# 06-1G_Phy0.net
KiCad netlist of a schematic drawn in Altium Designer
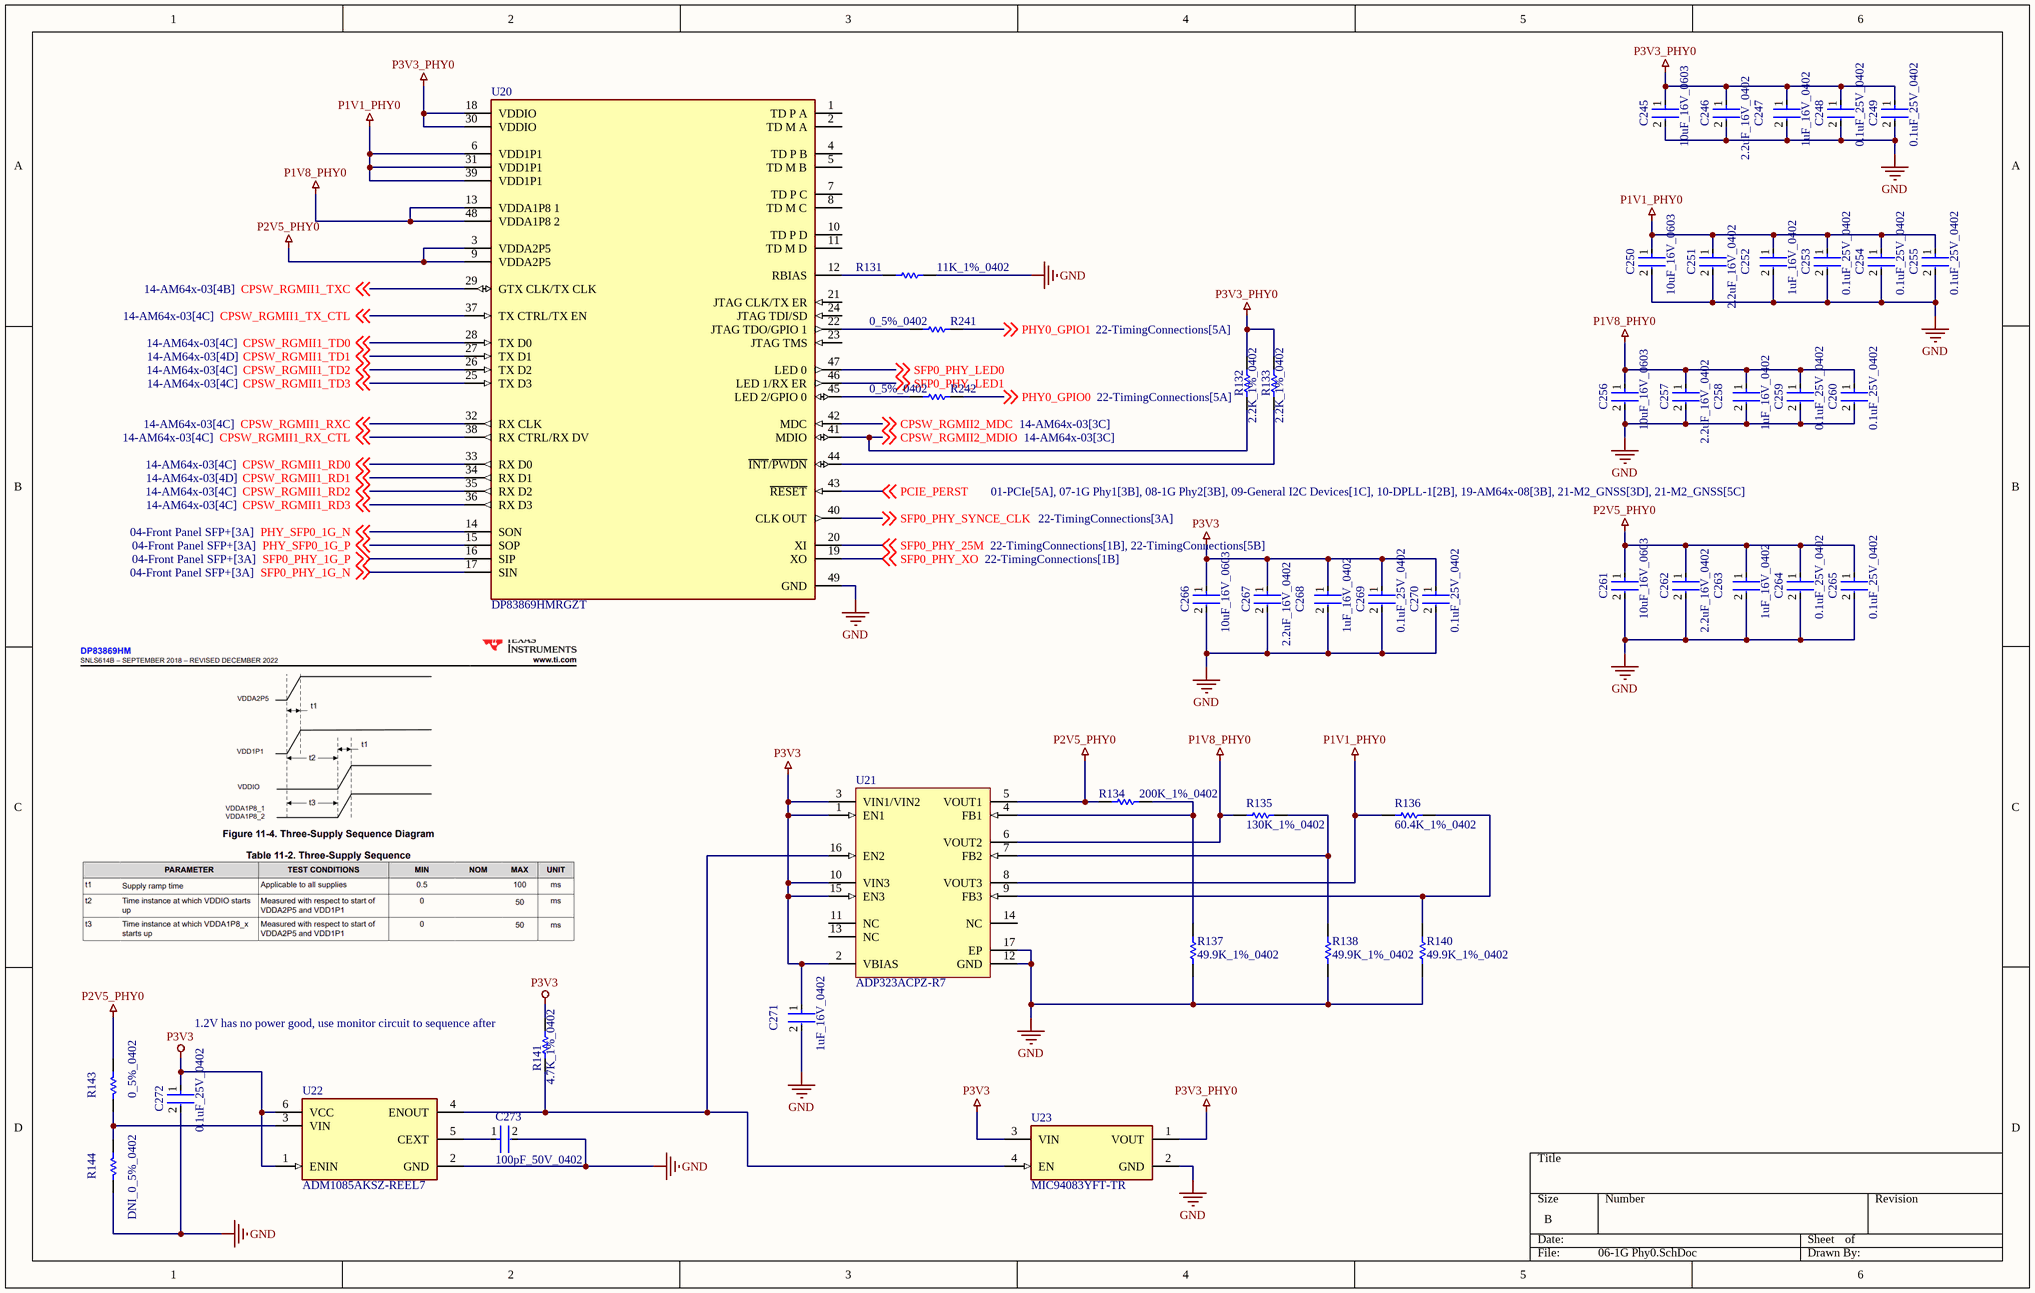
[diagram p0: 06-1G Phy0.SchDoc]

(export (version "E")
  (design (tool "Eeschema 10.0.6"))
  (components
    (comp (ref "C245")
      (value "10uF_16V_0603")
      (footprint "FP-0603-L_1_6_0_2-W_0_8_0-MFG")
      (description "Multilayer Ceramic Capacitor 10uF 16V X5R 20% SMD 0603 T/R")
      (fields (field (name "TOLERANCE") "20%"))
      (libsource (lib "Altium Content Vault") (part "b4654b650e69147ec39a6b967a45e02"))
    )
    (comp (ref "C246")
      (value "2.2uF_16V_0402")
      (footprint "FP-C1005-050-0_05-IPC_A")
      (description "Multilayer Ceramic Capacitors 2.2μF ±10% 16V X5R SMD 0402")
      (fields (field (name "TOLERANCE") "10%"))
      (libsource (lib "Altium Content Vault") (part "b4654b650e69147ec39a6b967a45e02"))
    )
    (comp (ref "C247")
      (value "1uF_16V_0402")
      (footprint "FP-0402-L_1_0_0_05-W_0_5-IPC_A")
      (description "None")
      (fields (field (name "TOLERANCE") "10%"))
      (libsource (lib "Altium Content Vault") (part "b4654b650e69147ec39a6b967a45e02"))
    )
    (comp (ref "C248")
      (value "0.1uF_25V_0402")
      (footprint "FP-0402-L_1_0_1-W_0_5_0_1-IPC_C")
      (description "General Purpose Ceramic Capacitor, 0402, 100nF, 10%, X7R, 15%, 25V")
      (fields (field (name "VOLTAGE") "25V") (field (name "TOLERANCE") "10%"))
      (libsource (lib "Altium Content Vault") (part "b4654b650e69147ec39a6b967a45e02"))
    )
    (comp (ref "C249")
      (value "0.1uF_25V_0402")
      (footprint "FP-0402-L_1_0_1-W_0_5_0_1-IPC_C")
      (description "General Purpose Ceramic Capacitor, 0402, 100nF, 10%, X7R, 15%, 25V")
      (fields (field (name "VOLTAGE") "25V") (field (name "TOLERANCE") "10%"))
      (libsource (lib "Altium Content Vault") (part "b4654b650e69147ec39a6b967a45e02"))
    )
    (comp (ref "C250")
      (value "10uF_16V_0603")
      (footprint "FP-0603-L_1_6_0_2-W_0_8_0-MFG")
      (description "Multilayer Ceramic Capacitor 10uF 16V X5R 20% SMD 0603 T/R")
      (fields (field (name "TOLERANCE") "20%"))
      (libsource (lib "Altium Content Vault") (part "b4654b650e69147ec39a6b967a45e02"))
    )
    (comp (ref "C251")
      (value "2.2uF_16V_0402")
      (footprint "FP-C1005-050-0_05-IPC_A")
      (description "Multilayer Ceramic Capacitors 2.2μF ±10% 16V X5R SMD 0402")
      (fields (field (name "TOLERANCE") "10%"))
      (libsource (lib "Altium Content Vault") (part "b4654b650e69147ec39a6b967a45e02"))
    )
    (comp (ref "C252")
      (value "1uF_16V_0402")
      (footprint "FP-0402-L_1_0_0_05-W_0_5-IPC_A")
      (description "None")
      (fields (field (name "TOLERANCE") "10%"))
      (libsource (lib "Altium Content Vault") (part "b4654b650e69147ec39a6b967a45e02"))
    )
    (comp (ref "C253")
      (value "0.1uF_25V_0402")
      (footprint "FP-0402-L_1_0_1-W_0_5_0_1-IPC_C")
      (description "General Purpose Ceramic Capacitor, 0402, 100nF, 10%, X7R, 15%, 25V")
      (fields (field (name "VOLTAGE") "25V") (field (name "TOLERANCE") "10%"))
      (libsource (lib "Altium Content Vault") (part "b4654b650e69147ec39a6b967a45e02"))
    )
    (comp (ref "C254")
      (value "0.1uF_25V_0402")
      (footprint "FP-0402-L_1_0_1-W_0_5_0_1-IPC_C")
      (description "General Purpose Ceramic Capacitor, 0402, 100nF, 10%, X7R, 15%, 25V")
      (fields (field (name "VOLTAGE") "25V") (field (name "TOLERANCE") "10%"))
      (libsource (lib "Altium Content Vault") (part "b4654b650e69147ec39a6b967a45e02"))
    )
    (comp (ref "C255")
      (value "0.1uF_25V_0402")
      (footprint "FP-0402-L_1_0_1-W_0_5_0_1-IPC_C")
      (description "General Purpose Ceramic Capacitor, 0402, 100nF, 10%, X7R, 15%, 25V")
      (fields (field (name "VOLTAGE") "25V") (field (name "TOLERANCE") "10%"))
      (libsource (lib "Altium Content Vault") (part "b4654b650e69147ec39a6b967a45e02"))
    )
    (comp (ref "C256")
      (value "10uF_16V_0603")
      (footprint "FP-0603-L_1_6_0_2-W_0_8_0-MFG")
      (description "Multilayer Ceramic Capacitor 10uF 16V X5R 20% SMD 0603 T/R")
      (fields (field (name "TOLERANCE") "20%"))
      (libsource (lib "Altium Content Vault") (part "b4654b650e69147ec39a6b967a45e02"))
    )
    (comp (ref "C257")
      (value "2.2uF_16V_0402")
      (footprint "FP-C1005-050-0_05-IPC_A")
      (description "Multilayer Ceramic Capacitors 2.2μF ±10% 16V X5R SMD 0402")
      (fields (field (name "TOLERANCE") "10%"))
      (libsource (lib "Altium Content Vault") (part "b4654b650e69147ec39a6b967a45e02"))
    )
    (comp (ref "C258")
      (value "1uF_16V_0402")
      (footprint "FP-0402-L_1_0_0_05-W_0_5-IPC_A")
      (description "None")
      (fields (field (name "TOLERANCE") "10%"))
      (libsource (lib "Altium Content Vault") (part "b4654b650e69147ec39a6b967a45e02"))
    )
    (comp (ref "C259")
      (value "0.1uF_25V_0402")
      (footprint "FP-0402-L_1_0_1-W_0_5_0_1-IPC_C")
      (description "General Purpose Ceramic Capacitor, 0402, 100nF, 10%, X7R, 15%, 25V")
      (fields (field (name "VOLTAGE") "25V") (field (name "TOLERANCE") "10%"))
      (libsource (lib "Altium Content Vault") (part "b4654b650e69147ec39a6b967a45e02"))
    )
    (comp (ref "C260")
      (value "0.1uF_25V_0402")
      (footprint "FP-0402-L_1_0_1-W_0_5_0_1-IPC_C")
      (description "General Purpose Ceramic Capacitor, 0402, 100nF, 10%, X7R, 15%, 25V")
      (fields (field (name "VOLTAGE") "25V") (field (name "TOLERANCE") "10%"))
      (libsource (lib "Altium Content Vault") (part "b4654b650e69147ec39a6b967a45e02"))
    )
    (comp (ref "C261")
      (value "10uF_16V_0603")
      (footprint "FP-0603-L_1_6_0_2-W_0_8_0-MFG")
      (description "Multilayer Ceramic Capacitor 10uF 16V X5R 20% SMD 0603 T/R")
      (fields (field (name "TOLERANCE") "20%"))
      (libsource (lib "Altium Content Vault") (part "b4654b650e69147ec39a6b967a45e02"))
    )
    (comp (ref "C262")
      (value "2.2uF_16V_0402")
      (footprint "FP-C1005-050-0_05-IPC_A")
      (description "Multilayer Ceramic Capacitors 2.2μF ±10% 16V X5R SMD 0402")
      (fields (field (name "TOLERANCE") "10%"))
      (libsource (lib "Altium Content Vault") (part "b4654b650e69147ec39a6b967a45e02"))
    )
    (comp (ref "C263")
      (value "1uF_16V_0402")
      (footprint "FP-0402-L_1_0_0_05-W_0_5-IPC_A")
      (description "None")
      (fields (field (name "TOLERANCE") "10%"))
      (libsource (lib "Altium Content Vault") (part "b4654b650e69147ec39a6b967a45e02"))
    )
    (comp (ref "C264")
      (value "0.1uF_25V_0402")
      (footprint "FP-0402-L_1_0_1-W_0_5_0_1-IPC_C")
      (description "General Purpose Ceramic Capacitor, 0402, 100nF, 10%, X7R, 15%, 25V")
      (fields (field (name "VOLTAGE") "25V") (field (name "TOLERANCE") "10%"))
      (libsource (lib "Altium Content Vault") (part "b4654b650e69147ec39a6b967a45e02"))
    )
    (comp (ref "C265")
      (value "0.1uF_25V_0402")
      (footprint "FP-0402-L_1_0_1-W_0_5_0_1-IPC_C")
      (description "General Purpose Ceramic Capacitor, 0402, 100nF, 10%, X7R, 15%, 25V")
      (fields (field (name "VOLTAGE") "25V") (field (name "TOLERANCE") "10%"))
      (libsource (lib "Altium Content Vault") (part "b4654b650e69147ec39a6b967a45e02"))
    )
    (comp (ref "C266")
      (value "10uF_16V_0603")
      (footprint "FP-0603-L_1_6_0_2-W_0_8_0-MFG")
      (description "Multilayer Ceramic Capacitor 10uF 16V X5R 20% SMD 0603 T/R")
      (fields (field (name "TOLERANCE") "20%"))
      (libsource (lib "Altium Content Vault") (part "b4654b650e69147ec39a6b967a45e02"))
    )
    (comp (ref "C267")
      (value "2.2uF_16V_0402")
      (footprint "FP-C1005-050-0_05-IPC_A")
      (description "Multilayer Ceramic Capacitors 2.2μF ±10% 16V X5R SMD 0402")
      (fields (field (name "TOLERANCE") "10%"))
      (libsource (lib "Altium Content Vault") (part "b4654b650e69147ec39a6b967a45e02"))
    )
    (comp (ref "C268")
      (value "1uF_16V_0402")
      (footprint "FP-0402-L_1_0_0_05-W_0_5-IPC_A")
      (description "None")
      (fields (field (name "TOLERANCE") "10%"))
      (libsource (lib "Altium Content Vault") (part "b4654b650e69147ec39a6b967a45e02"))
    )
    (comp (ref "C269")
      (value "0.1uF_25V_0402")
      (footprint "FP-0402-L_1_0_1-W_0_5_0_1-IPC_C")
      (description "General Purpose Ceramic Capacitor, 0402, 100nF, 10%, X7R, 15%, 25V")
      (fields (field (name "VOLTAGE") "25V") (field (name "TOLERANCE") "10%"))
      (libsource (lib "Altium Content Vault") (part "b4654b650e69147ec39a6b967a45e02"))
    )
    (comp (ref "C270")
      (value "0.1uF_25V_0402")
      (footprint "FP-0402-L_1_0_1-W_0_5_0_1-IPC_C")
      (description "General Purpose Ceramic Capacitor, 0402, 100nF, 10%, X7R, 15%, 25V")
      (fields (field (name "VOLTAGE") "25V") (field (name "TOLERANCE") "10%"))
      (libsource (lib "Altium Content Vault") (part "b4654b650e69147ec39a6b967a45e02"))
    )
    (comp (ref "C271")
      (value "1uF_16V_0402")
      (footprint "FP-0402-L_1_0_0_05-W_0_5-IPC_A")
      (description "None")
      (fields (field (name "TOLERANCE") "10%"))
      (libsource (lib "Altium Content Vault") (part "b4654b650e69147ec39a6b967a45e02"))
    )
    (comp (ref "C272")
      (value "0.1uF_25V_0402")
      (footprint "FP-0402-L_1_0_1-W_0_5_0_1-IPC_C")
      (description "General Purpose Ceramic Capacitor, 0402, 100nF, 10%, X7R, 15%, 25V")
      (fields (field (name "VOLTAGE") "25V") (field (name "TOLERANCE") "10%"))
      (libsource (lib "Altium Content Vault") (part "b4654b650e69147ec39a6b967a45e02"))
    )
    (comp (ref "C273")
      (value "100pF_50V_0402")
      (footprint "FP-C0402-BB-MFG")
      (description "CAP CER 100PF 50V C0G/NP0 0402")
      (fields (field (name "TOLERANCE") "0.02") (field (name "MANUFACTURER") "Kemet"))
      (libsource (lib "Altium Content Vault") (part "b4654b650e69147ec39a6b967a45e02"))
    )
    (comp (ref "R131")
      (value "11K_1%_0402")
      (footprint "RESC1005X40X25LL05T10")
      (fields (field (name "MANUFACTURER") "Yageo / Phycomp") (field (name "PART NUMBER") "RC0402FR-0711KL"))
      (libsource (lib "Altium Content Vault") (part "RES"))
    )
    (comp (ref "R132")
      (value "2.2K_1%_0402")
      (footprint "RESC1005X40X25ML10T10")
      (fields (field (name "PART NUMBER") "MC00625W040212K2") (field (name "MANUFACTURER") "Multicomp"))
      (libsource (lib "Altium Content Vault") (part "RES"))
    )
    (comp (ref "R133")
      (value "2.2K_1%_0402")
      (footprint "RESC1005X40X25ML10T10")
      (fields (field (name "PART NUMBER") "MC00625W040212K2") (field (name "MANUFACTURER") "Multicomp"))
      (libsource (lib "Altium Content Vault") (part "RES"))
    )
    (comp (ref "R134")
      (value "200K_1%_0402")
      (footprint "RESC1005X40X25LL10T10")
      (fields (field (name "PART NUMBER") "CR0402-FX-2003GLF") (field (name "MANUFACTURER") "Bourns"))
      (libsource (lib "Altium Content Vault") (part "RES"))
    )
    (comp (ref "R135")
      (value "130K_1%_0402")
      (footprint "RESC1005X40X25NL10T10")
      (fields
        (field (name "PART NUMBER") "CRG0402F130K")
        (field (name "MANUFACTURER") "TE Connectivity / AMP")
      )
      (libsource (lib "Altium Content Vault") (part "RES"))
    )
    (comp (ref "R136")
      (value "60.4K_1%_0402")
      (footprint "RESC1005X40X25LL05T10")
      (fields (field (name "MANUFACTURER") "Yageo / Phycomp") (field (name "PART NUMBER") "RC0402FR-0760K4L"))
      (libsource (lib "Altium Content Vault") (part "RES"))
    )
    (comp (ref "R137")
      (value "49.9K_1%_0402")
      (footprint "RESC1005X40X25LL10T10")
      (fields (field (name "MANUFACTURER") "Bourns") (field (name "PART NUMBER") "CR0402-FX-4992GLF"))
      (libsource (lib "Altium Content Vault") (part "RES"))
    )
    (comp (ref "R138")
      (value "49.9K_1%_0402")
      (footprint "RESC1005X40X25LL10T10")
      (fields (field (name "MANUFACTURER") "Bourns") (field (name "PART NUMBER") "CR0402-FX-4992GLF"))
      (libsource (lib "Altium Content Vault") (part "RES"))
    )
    (comp (ref "R140")
      (value "49.9K_1%_0402")
      (footprint "RESC1005X40X25LL10T10")
      (fields (field (name "MANUFACTURER") "Bourns") (field (name "PART NUMBER") "CR0402-FX-4992GLF"))
      (libsource (lib "Altium Content Vault") (part "RES"))
    )
    (comp (ref "R141")
      (value "4.7K_1%_0402")
      (footprint "RESC1005X40X25NL10T10")
      (fields (field (name "MANUFACTURER") "Bourns") (field (name "PART NUMBER") "CR0402-FX-4701GLF"))
      (libsource (lib "Altium Content Vault") (part "RES"))
    )
    (comp (ref "R143")
      (value "0_5%_0402")
      (footprint "RESC1005X40X25LL10T10")
      (fields (field (name "MANUFACTURER") "KOA Speer") (field (name "PART NUMBER") "RK73Z1ETTP"))
      (libsource (lib "Altium Content Vault") (part "RES"))
    )
    (comp (ref "R144")
      (value "DNI_0_5%_0402")
      (footprint "RESC1005X40X25LL10T10")
      (fields (field (name "MANUFACTURER") "KOA Speer") (field (name "PART NUMBER") "RK73Z1ETTP"))
      (libsource (lib "Altium Content Vault") (part "RES"))
    )
    (comp (ref "R241")
      (value "0_5%_0402")
      (footprint "RESC1005X40X25LL10T10")
      (fields (field (name "MANUFACTURER") "KOA Speer") (field (name "PART NUMBER") "RK73Z1ETTP"))
      (libsource (lib "Altium Content Vault") (part "RES"))
    )
    (comp (ref "R242")
      (value "0_5%_0402")
      (footprint "RESC1005X40X25LL10T10")
      (fields (field (name "MANUFACTURER") "KOA Speer") (field (name "PART NUMBER") "RK73Z1ETTP"))
      (libsource (lib "Altium Content Vault") (part "RES"))
    )
    (comp (ref "U20")
      (value "DP83869HMRGZT")
      (footprint "FP-RGZ0048B-IPC_A")
      (description "IC TRANSCEIVER 1/1 48FN")
      (libsource (lib "Altium Content Vault") (part "90cc30aaca705ff2adc2433a1cc0005"))
    )
    (comp (ref "U21")
      (value "ADP323ACPZ-R7")
      (footprint "ADI-CP-16-27_N")
      (fields (field (name "MANUFACTURER") "Analog Devices"))
      (libsource (lib "Altium Content Vault") (part "ADI-ADP323-CP-16-27"))
    )
    (comp (ref "U22")
      (value "ADM1085AKSZ-REEL7")
      (footprint "FP-KS-6-IPC_B")
      (description "IC SUPERVISOR 1 CHANNEL SC70-6")
      (libsource (lib "Altium Content Vault") (part "4d0b74b7e8e8a1541abc8f47282371d"))
    )
    (comp (ref "U23")
      (value "MIC94083YFT-TR")
      (footprint "FP-FTDFN085085-4LD-PL-1-MFG")
      (description "IC PWR SWITCH P-CHAN 1:1 4TMLF")
      (libsource (lib "Altium Content Vault") (part "f982b0e4379ad1be1c154354d61e319"))
    )
  )
  (nets
    (net (code "1") (name "CPSW_RGMII1_RD0") (class "Default")
      (node (ref "U20") (pin "33") (pinfunction "RX_D0_33") (pintype "output"))
    )
    (net (code "2") (name "CPSW_RGMII1_RD1") (class "Default")
      (node (ref "U20") (pin "34") (pinfunction "RX_D1_34") (pintype "output"))
    )
    (net (code "3") (name "CPSW_RGMII1_RD2") (class "Default")
      (node (ref "U20") (pin "35") (pinfunction "RX_D2_35") (pintype "output"))
    )
    (net (code "4") (name "CPSW_RGMII1_RD3") (class "Default")
      (node (ref "U20") (pin "36") (pinfunction "RX_D3_36") (pintype "output"))
    )
    (net (code "5") (name "CPSW_RGMII1_RXC") (class "Default")
      (node (ref "U20") (pin "32") (pinfunction "RX_CLK_32") (pintype "output"))
    )
    (net (code "6") (name "CPSW_RGMII1_RX_CTL") (class "Default")
      (node (ref "U20") (pin "38") (pinfunction "RX_CTRL/RX_DV_38") (pintype "output"))
    )
    (net (code "7") (name "CPSW_RGMII1_TD0") (class "Default")
      (node (ref "U20") (pin "28") (pinfunction "TX_D0_28") (pintype "input"))
    )
    (net (code "8") (name "CPSW_RGMII1_TD1") (class "Default")
      (node (ref "U20") (pin "27") (pinfunction "TX_D1_27") (pintype "input"))
    )
    (net (code "9") (name "CPSW_RGMII1_TD2") (class "Default")
      (node (ref "U20") (pin "26") (pinfunction "TX_D2_26") (pintype "input"))
    )
    (net (code "10") (name "CPSW_RGMII1_TD3") (class "Default")
      (node (ref "U20") (pin "25") (pinfunction "TX_D3_25") (pintype "input"))
    )
    (net (code "11") (name "CPSW_RGMII1_TXC") (class "Default")
      (node (ref "U20") (pin "29") (pinfunction "GTX_CLK/TX_CLK_29") (pintype "bidirectional"))
    )
    (net (code "12") (name "CPSW_RGMII1_TX_CTL") (class "Default")
      (node (ref "U20") (pin "37") (pinfunction "TX_CTRL/TX_EN_37") (pintype "input"))
    )
    (net (code "13") (name "CPSW_RGMII2_MDC") (class "Default")
      (node (ref "U20") (pin "42") (pinfunction "MDC_42") (pintype "input"))
    )
    (net (code "14") (name "CPSW_RGMII2_MDIO") (class "Default")
      (node (ref "R132") (pin "1") (pinfunction "1_1") (pintype "passive"))
      (node (ref "U20") (pin "41") (pinfunction "MDIO_41") (pintype "bidirectional"))
    )
    (net (code "15") (name "GND") (class "Default")
      (node (ref "C245") (pin "2") (pinfunction "2_2") (pintype "passive"))
      (node (ref "C246") (pin "2") (pinfunction "2_2") (pintype "passive"))
      (node (ref "C247") (pin "2") (pinfunction "2_2") (pintype "passive"))
      (node (ref "C248") (pin "2") (pinfunction "2_2") (pintype "passive"))
      (node (ref "C249") (pin "2") (pinfunction "2_2") (pintype "passive"))
      (node (ref "C250") (pin "2") (pinfunction "2_2") (pintype "passive"))
      (node (ref "C251") (pin "2") (pinfunction "2_2") (pintype "passive"))
      (node (ref "C252") (pin "2") (pinfunction "2_2") (pintype "passive"))
      (node (ref "C253") (pin "2") (pinfunction "2_2") (pintype "passive"))
      (node (ref "C254") (pin "2") (pinfunction "2_2") (pintype "passive"))
      (node (ref "C255") (pin "2") (pinfunction "2_2") (pintype "passive"))
      (node (ref "C256") (pin "2") (pinfunction "2_2") (pintype "passive"))
      (node (ref "C257") (pin "2") (pinfunction "2_2") (pintype "passive"))
      (node (ref "C258") (pin "2") (pinfunction "2_2") (pintype "passive"))
      (node (ref "C259") (pin "2") (pinfunction "2_2") (pintype "passive"))
      (node (ref "C260") (pin "2") (pinfunction "2_2") (pintype "passive"))
      (node (ref "C261") (pin "2") (pinfunction "2_2") (pintype "passive"))
      (node (ref "C262") (pin "2") (pinfunction "2_2") (pintype "passive"))
      (node (ref "C263") (pin "2") (pinfunction "2_2") (pintype "passive"))
      (node (ref "C264") (pin "2") (pinfunction "2_2") (pintype "passive"))
      (node (ref "C265") (pin "2") (pinfunction "2_2") (pintype "passive"))
      (node (ref "C266") (pin "2") (pinfunction "2_2") (pintype "passive"))
      (node (ref "C267") (pin "2") (pinfunction "2_2") (pintype "passive"))
      (node (ref "C268") (pin "2") (pinfunction "2_2") (pintype "passive"))
      (node (ref "C269") (pin "2") (pinfunction "2_2") (pintype "passive"))
      (node (ref "C270") (pin "2") (pinfunction "2_2") (pintype "passive"))
      (node (ref "C271") (pin "2") (pinfunction "2_2") (pintype "passive"))
      (node (ref "C272") (pin "2") (pinfunction "2_2") (pintype "passive"))
      (node (ref "C273") (pin "2") (pinfunction "2_2") (pintype "passive"))
      (node (ref "R131") (pin "2") (pinfunction "2_2") (pintype "passive"))
      (node (ref "R137") (pin "1") (pinfunction "1_1") (pintype "passive"))
      (node (ref "R138") (pin "1") (pinfunction "1_1") (pintype "passive"))
      (node (ref "R140") (pin "1") (pinfunction "1_1") (pintype "passive"))
      (node (ref "R144") (pin "2") (pinfunction "2_2") (pintype "passive"))
      (node (ref "U20") (pin "49") (pinfunction "GND_49") (pintype "power_in"))
      (node (ref "U21") (pin "12") (pinfunction "GND_12") (pintype "power_in"))
      (node (ref "U21") (pin "17") (pinfunction "EP_17") (pintype "power_in"))
      (node (ref "U22") (pin "2") (pinfunction "GND_2") (pintype "power_in"))
      (node (ref "U23") (pin "2") (pinfunction "GND_2") (pintype "power_in"))
    )
    (net (code "16") (name "Net-(U20-JTAG_TDO{slash}GPIO_1)") (class "Default")
      (node (ref "R241") (pin "1") (pinfunction "1_1") (pintype "passive"))
      (node (ref "U20") (pin "22") (pinfunction "JTAG_TDO/GPIO_1_22") (pintype "output"))
    )
    (net (code "17") (name "Net-(U20-LED_2{slash}GPIO_0)") (class "Default")
      (node (ref "R242") (pin "1") (pinfunction "1_1") (pintype "passive"))
      (node (ref "U20") (pin "45") (pinfunction "LED_2/GPIO_0_45") (pintype "bidirectional"))
    )
    (net (code "18") (name "Net-(U20-RBIAS)") (class "Default")
      (node (ref "R131") (pin "1") (pinfunction "1_1") (pintype "passive"))
      (node (ref "U20") (pin "12") (pinfunction "RBIAS_12") (pintype "passive"))
    )
    (net (code "19") (name "Net-(U20-~{INT}{slash}~{PWDN})") (class "Default")
      (node (ref "R133") (pin "1") (pinfunction "1_1") (pintype "passive"))
      (node (ref "U20") (pin "44") (pinfunction "~{INT}/~{PWDN}_44") (pintype "bidirectional"))
    )
    (net (code "20") (name "Net-(U21-EN2)") (class "Default")
      (node (ref "R141") (pin "2") (pinfunction "2_2") (pintype "passive"))
      (node (ref "U21") (pin "16") (pinfunction "EN2_16") (pintype "input"))
      (node (ref "U22") (pin "4") (pinfunction "ENOUT_4") (pintype "open_collector"))
      (node (ref "U23") (pin "4") (pinfunction "EN_4") (pintype "input"))
    )
    (net (code "21") (name "Net-(U21-FB1)") (class "Default")
      (node (ref "R134") (pin "2") (pinfunction "2_2") (pintype "passive"))
      (node (ref "R137") (pin "2") (pinfunction "2_2") (pintype "passive"))
      (node (ref "U21") (pin "4") (pinfunction "FB1_4") (pintype "input"))
    )
    (net (code "22") (name "Net-(U21-FB2)") (class "Default")
      (node (ref "R135") (pin "2") (pinfunction "2_2") (pintype "passive"))
      (node (ref "R138") (pin "2") (pinfunction "2_2") (pintype "passive"))
      (node (ref "U21") (pin "7") (pinfunction "FB2_7") (pintype "input"))
    )
    (net (code "23") (name "Net-(U21-FB3)") (class "Default")
      (node (ref "R136") (pin "2") (pinfunction "2_2") (pintype "passive"))
      (node (ref "R140") (pin "2") (pinfunction "2_2") (pintype "passive"))
      (node (ref "U21") (pin "9") (pinfunction "FB3_9") (pintype "input"))
    )
    (net (code "24") (name "Net-(U22-CEXT)") (class "Default")
      (node (ref "C273") (pin "1") (pinfunction "1_1") (pintype "passive"))
      (node (ref "U22") (pin "5") (pinfunction "CEXT_5") (pintype "passive"))
    )
    (net (code "25") (name "Net-(U22-VIN)") (class "Default")
      (node (ref "R143") (pin "2") (pinfunction "2_2") (pintype "passive"))
      (node (ref "R144") (pin "1") (pinfunction "1_1") (pintype "passive"))
      (node (ref "U22") (pin "3") (pinfunction "VIN_3") (pintype "power_in"))
    )
    (net (code "26") (name "P1V1_PHY0") (class "Default")
      (node (ref "C250") (pin "1") (pinfunction "1_1") (pintype "passive"))
      (node (ref "C251") (pin "1") (pinfunction "1_1") (pintype "passive"))
      (node (ref "C252") (pin "1") (pinfunction "1_1") (pintype "passive"))
      (node (ref "C253") (pin "1") (pinfunction "1_1") (pintype "passive"))
      (node (ref "C254") (pin "1") (pinfunction "1_1") (pintype "passive"))
      (node (ref "C255") (pin "1") (pinfunction "1_1") (pintype "passive"))
      (node (ref "R136") (pin "1") (pinfunction "1_1") (pintype "passive"))
      (node (ref "U20") (pin "31") (pinfunction "VDD1P1_31") (pintype "power_in"))
      (node (ref "U20") (pin "39") (pinfunction "VDD1P1_39") (pintype "power_in"))
      (node (ref "U20") (pin "6") (pinfunction "VDD1P1_6") (pintype "power_in"))
      (node (ref "U21") (pin "8") (pinfunction "VOUT3_8") (pintype "power_in"))
    )
    (net (code "27") (name "P1V8_PHY0") (class "Default")
      (node (ref "C256") (pin "1") (pinfunction "1_1") (pintype "passive"))
      (node (ref "C257") (pin "1") (pinfunction "1_1") (pintype "passive"))
      (node (ref "C258") (pin "1") (pinfunction "1_1") (pintype "passive"))
      (node (ref "C259") (pin "1") (pinfunction "1_1") (pintype "passive"))
      (node (ref "C260") (pin "1") (pinfunction "1_1") (pintype "passive"))
      (node (ref "R135") (pin "1") (pinfunction "1_1") (pintype "passive"))
      (node (ref "U20") (pin "13") (pinfunction "VDDA1P8_1_13") (pintype "power_in"))
      (node (ref "U20") (pin "48") (pinfunction "VDDA1P8_2_48") (pintype "power_in"))
      (node (ref "U21") (pin "6") (pinfunction "VOUT2_6") (pintype "power_in"))
    )
    (net (code "28") (name "P2V5_PHY0") (class "Default")
      (node (ref "C261") (pin "1") (pinfunction "1_1") (pintype "passive"))
      (node (ref "C262") (pin "1") (pinfunction "1_1") (pintype "passive"))
      (node (ref "C263") (pin "1") (pinfunction "1_1") (pintype "passive"))
      (node (ref "C264") (pin "1") (pinfunction "1_1") (pintype "passive"))
      (node (ref "C265") (pin "1") (pinfunction "1_1") (pintype "passive"))
      (node (ref "R134") (pin "1") (pinfunction "1_1") (pintype "passive"))
      (node (ref "R143") (pin "1") (pinfunction "1_1") (pintype "passive"))
      (node (ref "U20") (pin "3") (pinfunction "VDDA2P5_3") (pintype "power_in"))
      (node (ref "U20") (pin "9") (pinfunction "VDDA2P5_9") (pintype "power_in"))
      (node (ref "U21") (pin "5") (pinfunction "VOUT1_5") (pintype "power_in"))
    )
    (net (code "29") (name "P3V3") (class "Default")
      (node (ref "C266") (pin "1") (pinfunction "1_1") (pintype "passive"))
      (node (ref "C267") (pin "1") (pinfunction "1_1") (pintype "passive"))
      (node (ref "C268") (pin "1") (pinfunction "1_1") (pintype "passive"))
      (node (ref "C269") (pin "1") (pinfunction "1_1") (pintype "passive"))
      (node (ref "C270") (pin "1") (pinfunction "1_1") (pintype "passive"))
      (node (ref "C271") (pin "1") (pinfunction "1_1") (pintype "passive"))
      (node (ref "C272") (pin "1") (pinfunction "1_1") (pintype "passive"))
      (node (ref "R141") (pin "1") (pinfunction "1_1") (pintype "passive"))
      (node (ref "U21") (pin "1") (pinfunction "EN1_1") (pintype "input"))
      (node (ref "U21") (pin "10") (pinfunction "VIN3_10") (pintype "power_in"))
      (node (ref "U21") (pin "15") (pinfunction "EN3_15") (pintype "input"))
      (node (ref "U21") (pin "2") (pinfunction "VBIAS_2") (pintype "power_in"))
      (node (ref "U21") (pin "3") (pinfunction "VIN1/VIN2_3") (pintype "power_in"))
      (node (ref "U22") (pin "1") (pinfunction "ENIN_1") (pintype "input"))
      (node (ref "U22") (pin "6") (pinfunction "VCC_6") (pintype "power_in"))
      (node (ref "U23") (pin "3") (pinfunction "VIN_3") (pintype "power_in"))
    )
    (net (code "30") (name "P3V3_PHY0") (class "Default")
      (node (ref "C245") (pin "1") (pinfunction "1_1") (pintype "passive"))
      (node (ref "C246") (pin "1") (pinfunction "1_1") (pintype "passive"))
      (node (ref "C247") (pin "1") (pinfunction "1_1") (pintype "passive"))
      (node (ref "C248") (pin "1") (pinfunction "1_1") (pintype "passive"))
      (node (ref "C249") (pin "1") (pinfunction "1_1") (pintype "passive"))
      (node (ref "R132") (pin "2") (pinfunction "2_2") (pintype "passive"))
      (node (ref "R133") (pin "2") (pinfunction "2_2") (pintype "passive"))
      (node (ref "U20") (pin "18") (pinfunction "VDDIO_18") (pintype "power_in"))
      (node (ref "U20") (pin "30") (pinfunction "VDDIO_30") (pintype "power_in"))
      (node (ref "U23") (pin "1") (pinfunction "VOUT_1") (pintype "power_in"))
    )
    (net (code "31") (name "PCIE_PERST") (class "Default")
      (node (ref "U20") (pin "43") (pinfunction "~{RESET}_43") (pintype "input"))
    )
    (net (code "32") (name "PHY0_GPIO0") (class "Default")
      (node (ref "R242") (pin "2") (pinfunction "2_2") (pintype "passive"))
    )
    (net (code "33") (name "PHY0_GPIO1") (class "Default")
      (node (ref "R241") (pin "2") (pinfunction "2_2") (pintype "passive"))
    )
    (net (code "34") (name "PHY_SFP0_1G_N") (class "Default")
      (node (ref "U20") (pin "14") (pinfunction "SON_14") (pintype "passive"))
    )
    (net (code "35") (name "PHY_SFP0_1G_P") (class "Default")
      (node (ref "U20") (pin "15") (pinfunction "SOP_15") (pintype "passive"))
    )
    (net (code "36") (name "SFP0_PHY_1G_N") (class "Default")
      (node (ref "U20") (pin "17") (pinfunction "SIN_17") (pintype "passive"))
    )
    (net (code "37") (name "SFP0_PHY_1G_P") (class "Default")
      (node (ref "U20") (pin "16") (pinfunction "SIP_16") (pintype "passive"))
    )
    (net (code "38") (name "SFP0_PHY_25M") (class "Default")
      (node (ref "U20") (pin "20") (pinfunction "XI_20") (pintype "passive"))
    )
    (net (code "39") (name "SFP0_PHY_LED0") (class "Default")
      (node (ref "U20") (pin "47") (pinfunction "LED_0_47") (pintype "output"))
    )
    (net (code "40") (name "SFP0_PHY_LED1") (class "Default")
      (node (ref "U20") (pin "46") (pinfunction "LED_1/RX_ER_46") (pintype "output"))
    )
    (net (code "41") (name "SFP0_PHY_SYNCE_CLK") (class "Default")
      (node (ref "U20") (pin "40") (pinfunction "CLK_OUT_40") (pintype "output"))
    )
    (net (code "42") (name "SFP0_PHY_XO") (class "Default")
      (node (ref "U20") (pin "19") (pinfunction "XO_19") (pintype "passive"))
    )
    (net (code "43") (name "unconnected-(U20-JTAG_CLK{slash}TX_ER-Pad21)") (class "Default")
      (node (ref "U20") (pin "21") (pinfunction "JTAG_CLK/TX_ER_21") (pintype "input"))
    )
    (net (code "44") (name "unconnected-(U20-JTAG_TDI{slash}SD-Pad24)") (class "Default")
      (node (ref "U20") (pin "24") (pinfunction "JTAG_TDI/SD_24") (pintype "input"))
    )
    (net (code "45") (name "unconnected-(U20-JTAG_TMS-Pad23)") (class "Default")
      (node (ref "U20") (pin "23") (pinfunction "JTAG_TMS_23") (pintype "input"))
    )
    (net (code "46") (name "unconnected-(U20-TD_M_A-Pad2)") (class "Default")
      (node (ref "U20") (pin "2") (pinfunction "TD_M_A_2") (pintype "passive"))
    )
    (net (code "47") (name "unconnected-(U20-TD_M_B-Pad5)") (class "Default")
      (node (ref "U20") (pin "5") (pinfunction "TD_M_B_5") (pintype "passive"))
    )
    (net (code "48") (name "unconnected-(U20-TD_M_C-Pad8)") (class "Default")
      (node (ref "U20") (pin "8") (pinfunction "TD_M_C_8") (pintype "passive"))
    )
    (net (code "49") (name "unconnected-(U20-TD_M_D-Pad11)") (class "Default")
      (node (ref "U20") (pin "11") (pinfunction "TD_M_D_11") (pintype "passive"))
    )
    (net (code "50") (name "unconnected-(U20-TD_P_A-Pad1)") (class "Default")
      (node (ref "U20") (pin "1") (pinfunction "TD_P_A_1") (pintype "passive"))
    )
    (net (code "51") (name "unconnected-(U20-TD_P_B-Pad4)") (class "Default")
      (node (ref "U20") (pin "4") (pinfunction "TD_P_B_4") (pintype "passive"))
    )
    (net (code "52") (name "unconnected-(U20-TD_P_C-Pad7)") (class "Default")
      (node (ref "U20") (pin "7") (pinfunction "TD_P_C_7") (pintype "passive"))
    )
    (net (code "53") (name "unconnected-(U20-TD_P_D-Pad10)") (class "Default")
      (node (ref "U20") (pin "10") (pinfunction "TD_P_D_10") (pintype "passive"))
    )
    (net (code "54") (name "unconnected-(U21-NC-Pad11)") (class "Default")
      (node (ref "U21") (pin "11") (pinfunction "NC_11") (pintype "passive"))
    )
    (net (code "55") (name "unconnected-(U21-NC-Pad13)") (class "Default")
      (node (ref "U21") (pin "13") (pinfunction "NC_13") (pintype "passive"))
    )
    (net (code "56") (name "unconnected-(U21-NC-Pad14)") (class "Default")
      (node (ref "U21") (pin "14") (pinfunction "NC_14") (pintype "passive"))
    )
  )
)
